# RF-detector.net
KiCad netlist of a schematic drawn in EAGLE
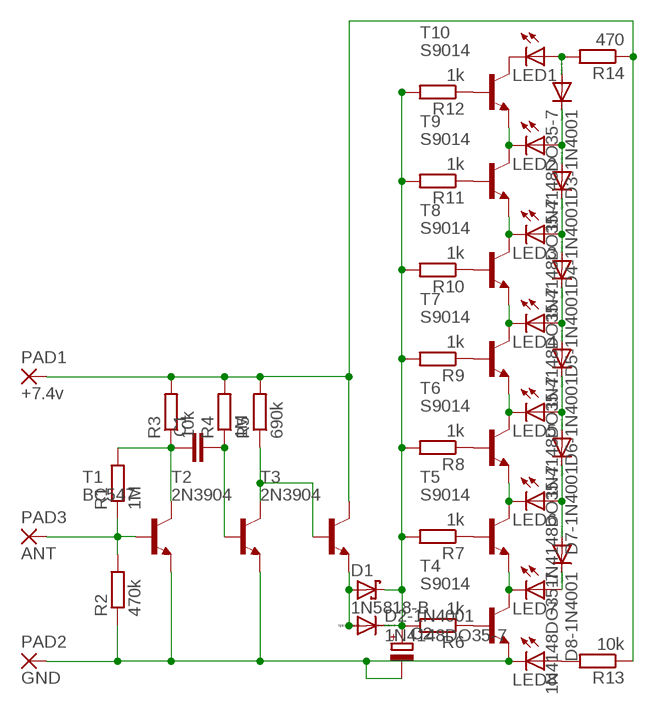
[diagram p0: schematic, sheet 1]

(export (version "E")
  (design (tool "Eeschema 10.0.6"))
  (components
    (comp (ref "C1")
      (value "C-EU050-024X044")
      (footprint "eagle-import:C050-024X044")
      (libsource (lib "eagle-import") (part "C-EU050-024X044"))
    )
    (comp (ref "C2")
      (value "CPOL-EUE1.8-4")
      (footprint "eagle-import:E1,8-4")
      (libsource (lib "eagle-import") (part "CPOL-EUE1.8-4"))
    )
    (comp (ref "D1")
      (value "1N5818-B")
      (footprint "eagle-import:DO41-7.6")
      (libsource (lib "eagle-import") (part "1N5818-B"))
    )
    (comp (ref "D2-1N4001")
      (value "1N4148DO35-7")
      (footprint "eagle-import:DO35-7")
      (libsource (lib "eagle-import") (part "1N4148DO35-7"))
    )
    (comp (ref "D3-1N4001")
      (value "1N4148DO35-7")
      (footprint "eagle-import:DO35-7")
      (libsource (lib "eagle-import") (part "1N4148DO35-7"))
    )
    (comp (ref "D4-1N4001")
      (value "1N4148DO35-7")
      (footprint "eagle-import:DO35-7")
      (libsource (lib "eagle-import") (part "1N4148DO35-7"))
    )
    (comp (ref "D5-1N4001")
      (value "1N4148DO35-7")
      (footprint "eagle-import:DO35-7")
      (libsource (lib "eagle-import") (part "1N4148DO35-7"))
    )
    (comp (ref "D6-1N4001")
      (value "1N4148DO35-7")
      (footprint "eagle-import:DO35-7")
      (libsource (lib "eagle-import") (part "1N4148DO35-7"))
    )
    (comp (ref "D7-1N4001")
      (value "1N4148DO35-7")
      (footprint "eagle-import:DO35-7")
      (libsource (lib "eagle-import") (part "1N4148DO35-7"))
    )
    (comp (ref "D8-1N4001")
      (value "1N4148DO35-7")
      (footprint "eagle-import:DO35-7")
      (libsource (lib "eagle-import") (part "1N4148DO35-7"))
    )
    (comp (ref "LED1")
      (value "LED3MM")
      (footprint "eagle-import:LED3MM")
      (libsource (lib "eagle-import") (part "LED3MM"))
    )
    (comp (ref "LED2")
      (value "LED3MM")
      (footprint "eagle-import:LED3MM")
      (libsource (lib "eagle-import") (part "LED3MM"))
    )
    (comp (ref "LED3")
      (value "LED3MM")
      (footprint "eagle-import:LED3MM")
      (libsource (lib "eagle-import") (part "LED3MM"))
    )
    (comp (ref "LED4")
      (value "LED3MM")
      (footprint "eagle-import:LED3MM")
      (libsource (lib "eagle-import") (part "LED3MM"))
    )
    (comp (ref "LED5")
      (value "LED3MM")
      (footprint "eagle-import:LED3MM")
      (libsource (lib "eagle-import") (part "LED3MM"))
    )
    (comp (ref "LED6")
      (value "LED3MM")
      (footprint "eagle-import:LED3MM")
      (libsource (lib "eagle-import") (part "LED3MM"))
    )
    (comp (ref "LED7")
      (value "LED3MM")
      (footprint "eagle-import:LED3MM")
      (libsource (lib "eagle-import") (part "LED3MM"))
    )
    (comp (ref "LED8")
      (value "LED3MM")
      (footprint "eagle-import:LED3MM")
      (libsource (lib "eagle-import") (part "LED3MM"))
    )
    (comp (ref "PAD1")
      (value "+7.4v")
      (footprint "eagle-import:2,54_0,8")
      (libsource (lib "eagle-import") (part "2,54/0,8"))
    )
    (comp (ref "PAD2")
      (value "GND")
      (footprint "eagle-import:2,54_0,8")
      (libsource (lib "eagle-import") (part "2,54/0,8"))
    )
    (comp (ref "PAD3")
      (value "ANT")
      (footprint "eagle-import:2,54_0,8")
      (libsource (lib "eagle-import") (part "2,54/0,8"))
    )
    (comp (ref "R1")
      (value "1M")
      (footprint "eagle-import:0204_7")
      (libsource (lib "eagle-import") (part "R-EU_0204/7"))
    )
    (comp (ref "R2")
      (value "470k")
      (footprint "eagle-import:0204_7")
      (libsource (lib "eagle-import") (part "R-EU_0204/7"))
    )
    (comp (ref "R3")
      (value "10k")
      (footprint "eagle-import:0204_7")
      (libsource (lib "eagle-import") (part "R-EU_0204/7"))
    )
    (comp (ref "R4")
      (value "1M")
      (footprint "eagle-import:0204_7")
      (libsource (lib "eagle-import") (part "R-EU_0204/7"))
    )
    (comp (ref "R5")
      (value "690k")
      (footprint "eagle-import:0204_7")
      (libsource (lib "eagle-import") (part "R-EU_0204/7"))
    )
    (comp (ref "R6")
      (value "1k")
      (footprint "eagle-import:0204_7")
      (libsource (lib "eagle-import") (part "R-EU_0204/7"))
    )
    (comp (ref "R7")
      (value "1k")
      (footprint "eagle-import:0204_7")
      (libsource (lib "eagle-import") (part "R-EU_0204/7"))
    )
    (comp (ref "R8")
      (value "1k")
      (footprint "eagle-import:0204_7")
      (libsource (lib "eagle-import") (part "R-EU_0204/7"))
    )
    (comp (ref "R9")
      (value "1k")
      (footprint "eagle-import:0204_7")
      (libsource (lib "eagle-import") (part "R-EU_0204/7"))
    )
    (comp (ref "R10")
      (value "1k")
      (footprint "eagle-import:0204_7")
      (libsource (lib "eagle-import") (part "R-EU_0204/7"))
    )
    (comp (ref "R11")
      (value "1k")
      (footprint "eagle-import:0204_7")
      (libsource (lib "eagle-import") (part "R-EU_0204/7"))
    )
    (comp (ref "R12")
      (value "1k")
      (footprint "eagle-import:0204_7")
      (libsource (lib "eagle-import") (part "R-EU_0204/7"))
    )
    (comp (ref "R13")
      (value "10k")
      (footprint "eagle-import:0204_7")
      (libsource (lib "eagle-import") (part "R-EU_0204/7"))
    )
    (comp (ref "R14")
      (value "470")
      (footprint "eagle-import:0204_7")
      (libsource (lib "eagle-import") (part "R-EU_0204/7"))
    )
    (comp (ref "T1")
      (value "BC547")
      (footprint "eagle-import:TO92")
      (libsource (lib "eagle-import") (part "BC547"))
    )
    (comp (ref "T2")
      (value "2N3904")
      (footprint "eagle-import:TO92")
      (libsource (lib "eagle-import") (part "2N3904"))
    )
    (comp (ref "T3")
      (value "2N3904")
      (footprint "eagle-import:TO92")
      (libsource (lib "eagle-import") (part "2N3904"))
    )
    (comp (ref "T4")
      (value "S9014")
      (footprint "eagle-import:TO92-EBC")
      (libsource (lib "eagle-import") (part "-NPN-TO92-EBC"))
    )
    (comp (ref "T5")
      (value "S9014")
      (footprint "eagle-import:TO92-EBC")
      (libsource (lib "eagle-import") (part "-NPN-TO92-EBC"))
    )
    (comp (ref "T6")
      (value "S9014")
      (footprint "eagle-import:TO92-EBC")
      (libsource (lib "eagle-import") (part "-NPN-TO92-EBC"))
    )
    (comp (ref "T7")
      (value "S9014")
      (footprint "eagle-import:TO92-EBC")
      (libsource (lib "eagle-import") (part "-NPN-TO92-EBC"))
    )
    (comp (ref "T8")
      (value "S9014")
      (footprint "eagle-import:TO92-EBC")
      (libsource (lib "eagle-import") (part "-NPN-TO92-EBC"))
    )
    (comp (ref "T9")
      (value "S9014")
      (footprint "eagle-import:TO92-EBC")
      (libsource (lib "eagle-import") (part "-NPN-TO92-EBC"))
    )
    (comp (ref "T10")
      (value "S9014")
      (footprint "eagle-import:TO92-EBC")
      (libsource (lib "eagle-import") (part "-NPN-TO92-EBC"))
    )
  )
  (nets
    (net (code "1") (name "Net-(C2-Pad+)") (class "Default")
      (node (ref "C2") (pin "+") (pinfunction "+_+") (pintype "passive"))
      (node (ref "D1") (pin "C") (pinfunction "C_C") (pintype "passive"))
      (node (ref "D2-1N4001") (pin "C") (pinfunction "C_C") (pintype "passive"))
      (node (ref "R10") (pin "2") (pinfunction "2_2") (pintype "passive"))
      (node (ref "R11") (pin "2") (pinfunction "2_2") (pintype "passive"))
      (node (ref "R12") (pin "2") (pinfunction "2_2") (pintype "passive"))
      (node (ref "R6") (pin "2") (pinfunction "2_2") (pintype "passive"))
      (node (ref "R7") (pin "2") (pinfunction "2_2") (pintype "passive"))
      (node (ref "R8") (pin "2") (pinfunction "2_2") (pintype "passive"))
      (node (ref "R9") (pin "2") (pinfunction "2_2") (pintype "passive"))
    )
    (net (code "2") (name "Net-(D3-1N4001-PadA)") (class "Default")
      (node (ref "D3-1N4001") (pin "A") (pinfunction "A_A") (pintype "passive"))
      (node (ref "LED1") (pin "A") (pinfunction "A_A") (pintype "passive"))
      (node (ref "R14") (pin "2") (pinfunction "2_2") (pintype "passive"))
    )
    (net (code "3") (name "Net-(D3-1N4001-PadC)") (class "Default")
      (node (ref "D3-1N4001") (pin "C") (pinfunction "C_C") (pintype "passive"))
      (node (ref "D4-1N4001") (pin "A") (pinfunction "A_A") (pintype "passive"))
      (node (ref "LED2") (pin "A") (pinfunction "A_A") (pintype "passive"))
    )
    (net (code "4") (name "Net-(D4-1N4001-PadC)") (class "Default")
      (node (ref "D4-1N4001") (pin "C") (pinfunction "C_C") (pintype "passive"))
      (node (ref "D5-1N4001") (pin "A") (pinfunction "A_A") (pintype "passive"))
      (node (ref "LED3") (pin "A") (pinfunction "A_A") (pintype "passive"))
    )
    (net (code "5") (name "Net-(D5-1N4001-PadC)") (class "Default")
      (node (ref "D5-1N4001") (pin "C") (pinfunction "C_C") (pintype "passive"))
      (node (ref "D6-1N4001") (pin "A") (pinfunction "A_A") (pintype "passive"))
      (node (ref "LED4") (pin "A") (pinfunction "A_A") (pintype "passive"))
    )
    (net (code "6") (name "Net-(D6-1N4001-PadC)") (class "Default")
      (node (ref "D6-1N4001") (pin "C") (pinfunction "C_C") (pintype "passive"))
      (node (ref "D7-1N4001") (pin "A") (pinfunction "A_A") (pintype "passive"))
      (node (ref "LED5") (pin "A") (pinfunction "A_A") (pintype "passive"))
    )
    (net (code "7") (name "Net-(D7-1N4001-PadC)") (class "Default")
      (node (ref "D7-1N4001") (pin "C") (pinfunction "C_C") (pintype "passive"))
      (node (ref "D8-1N4001") (pin "A") (pinfunction "A_A") (pintype "passive"))
      (node (ref "LED6") (pin "A") (pinfunction "A_A") (pintype "passive"))
    )
    (net (code "8") (name "Net-(D8-1N4001-PadC)") (class "Default")
      (node (ref "D8-1N4001") (pin "C") (pinfunction "C_C") (pintype "passive"))
      (node (ref "LED7") (pin "A") (pinfunction "A_A") (pintype "passive"))
    )
    (net (code "9") (name "Net-(LED1-C)") (class "Default")
      (node (ref "LED1") (pin "K") (pinfunction "C_K") (pintype "passive"))
      (node (ref "T10") (pin "C") (pinfunction "C_C") (pintype "passive"))
    )
    (net (code "10") (name "Net-(LED2-C)") (class "Default")
      (node (ref "LED2") (pin "K") (pinfunction "C_K") (pintype "passive"))
      (node (ref "T10") (pin "E") (pinfunction "E_E") (pintype "passive"))
      (node (ref "T9") (pin "C") (pinfunction "C_C") (pintype "passive"))
    )
    (net (code "11") (name "Net-(LED3-C)") (class "Default")
      (node (ref "LED3") (pin "K") (pinfunction "C_K") (pintype "passive"))
      (node (ref "T8") (pin "C") (pinfunction "C_C") (pintype "passive"))
      (node (ref "T9") (pin "E") (pinfunction "E_E") (pintype "passive"))
    )
    (net (code "12") (name "Net-(LED4-C)") (class "Default")
      (node (ref "LED4") (pin "K") (pinfunction "C_K") (pintype "passive"))
      (node (ref "T7") (pin "C") (pinfunction "C_C") (pintype "passive"))
      (node (ref "T8") (pin "E") (pinfunction "E_E") (pintype "passive"))
    )
    (net (code "13") (name "Net-(LED5-C)") (class "Default")
      (node (ref "LED5") (pin "K") (pinfunction "C_K") (pintype "passive"))
      (node (ref "T6") (pin "C") (pinfunction "C_C") (pintype "passive"))
      (node (ref "T7") (pin "E") (pinfunction "E_E") (pintype "passive"))
    )
    (net (code "14") (name "Net-(LED6-C)") (class "Default")
      (node (ref "LED6") (pin "K") (pinfunction "C_K") (pintype "passive"))
      (node (ref "T5") (pin "C") (pinfunction "C_C") (pintype "passive"))
      (node (ref "T6") (pin "E") (pinfunction "E_E") (pintype "passive"))
    )
    (net (code "15") (name "Net-(LED7-C)") (class "Default")
      (node (ref "LED7") (pin "K") (pinfunction "C_K") (pintype "passive"))
      (node (ref "T4") (pin "C") (pinfunction "C_C") (pintype "passive"))
      (node (ref "T5") (pin "E") (pinfunction "E_E") (pintype "passive"))
    )
    (net (code "16") (name "Net-(LED8-C)") (class "Default")
      (node (ref "C2") (pin "-") (pinfunction "-_-") (pintype "passive"))
      (node (ref "LED8") (pin "K") (pinfunction "C_K") (pintype "passive"))
      (node (ref "PAD2") (pin "1") (pinfunction "P_1") (pintype "passive"))
      (node (ref "R2") (pin "1") (pinfunction "1_1") (pintype "passive"))
      (node (ref "T1") (pin "1") (pinfunction "E_1") (pintype "passive"))
      (node (ref "T2") (pin "3") (pinfunction "E_3") (pintype "passive"))
      (node (ref "T4") (pin "E") (pinfunction "E_E") (pintype "passive"))
    )
    (net (code "17") (name "Net-(LED8-PadA)") (class "Default")
      (node (ref "LED8") (pin "A") (pinfunction "A_A") (pintype "passive"))
      (node (ref "R13") (pin "2") (pinfunction "2_2") (pintype "passive"))
    )
    (net (code "18") (name "Net-(PAD1-P)") (class "Default")
      (node (ref "PAD1") (pin "1") (pinfunction "P_1") (pintype "passive"))
      (node (ref "R13") (pin "1") (pinfunction "1_1") (pintype "passive"))
      (node (ref "R14") (pin "1") (pinfunction "1_1") (pintype "passive"))
      (node (ref "R3") (pin "2") (pinfunction "2_2") (pintype "passive"))
      (node (ref "R4") (pin "2") (pinfunction "2_2") (pintype "passive"))
      (node (ref "R5") (pin "2") (pinfunction "2_2") (pintype "passive"))
      (node (ref "T3") (pin "1") (pinfunction "C_1") (pintype "passive"))
    )
    (net (code "19") (name "Net-(PAD3-P)") (class "Default")
      (node (ref "PAD3") (pin "1") (pinfunction "P_1") (pintype "passive"))
      (node (ref "R1") (pin "1") (pinfunction "1_1") (pintype "passive"))
      (node (ref "R2") (pin "2") (pinfunction "2_2") (pintype "passive"))
      (node (ref "T1") (pin "2") (pinfunction "B_2") (pintype "passive"))
    )
    (net (code "20") (name "Net-(R6-Pad1)") (class "Default")
      (node (ref "R6") (pin "1") (pinfunction "1_1") (pintype "passive"))
      (node (ref "T4") (pin "B") (pinfunction "B_B") (pintype "passive"))
    )
    (net (code "21") (name "Net-(R7-Pad1)") (class "Default")
      (node (ref "R7") (pin "1") (pinfunction "1_1") (pintype "passive"))
      (node (ref "T5") (pin "B") (pinfunction "B_B") (pintype "passive"))
    )
    (net (code "22") (name "Net-(R8-Pad1)") (class "Default")
      (node (ref "R8") (pin "1") (pinfunction "1_1") (pintype "passive"))
      (node (ref "T6") (pin "B") (pinfunction "B_B") (pintype "passive"))
    )
    (net (code "23") (name "Net-(R9-Pad1)") (class "Default")
      (node (ref "R9") (pin "1") (pinfunction "1_1") (pintype "passive"))
      (node (ref "T7") (pin "B") (pinfunction "B_B") (pintype "passive"))
    )
    (net (code "24") (name "Net-(R10-Pad1)") (class "Default")
      (node (ref "R10") (pin "1") (pinfunction "1_1") (pintype "passive"))
      (node (ref "T8") (pin "B") (pinfunction "B_B") (pintype "passive"))
    )
    (net (code "25") (name "Net-(R11-Pad1)") (class "Default")
      (node (ref "R11") (pin "1") (pinfunction "1_1") (pintype "passive"))
      (node (ref "T9") (pin "B") (pinfunction "B_B") (pintype "passive"))
    )
    (net (code "26") (name "Net-(R12-Pad1)") (class "Default")
      (node (ref "R12") (pin "1") (pinfunction "1_1") (pintype "passive"))
      (node (ref "T10") (pin "B") (pinfunction "B_B") (pintype "passive"))
    )
    (net (code "27") (name "Net-(T1-C)") (class "Default")
      (node (ref "C1") (pin "1") (pinfunction "1_1") (pintype "passive"))
      (node (ref "R1") (pin "2") (pinfunction "2_2") (pintype "passive"))
      (node (ref "R3") (pin "1") (pinfunction "1_1") (pintype "passive"))
      (node (ref "T1") (pin "3") (pinfunction "C_3") (pintype "passive"))
    )
    (net (code "28") (name "Net-(T2-B)") (class "Default")
      (node (ref "C1") (pin "2") (pinfunction "2_2") (pintype "passive"))
      (node (ref "R4") (pin "1") (pinfunction "1_1") (pintype "passive"))
      (node (ref "T2") (pin "2") (pinfunction "B_2") (pintype "passive"))
    )
    (net (code "29") (name "Net-(T2-C)") (class "Default")
      (node (ref "R5") (pin "1") (pinfunction "1_1") (pintype "passive"))
      (node (ref "T2") (pin "1") (pinfunction "C_1") (pintype "passive"))
      (node (ref "T3") (pin "2") (pinfunction "B_2") (pintype "passive"))
    )
    (net (code "30") (name "Net-(T3-E)") (class "Default")
      (node (ref "D1") (pin "A") (pinfunction "A_A") (pintype "passive"))
      (node (ref "D2-1N4001") (pin "A") (pinfunction "A_A") (pintype "passive"))
      (node (ref "T3") (pin "3") (pinfunction "E_3") (pintype "passive"))
    )
  )
)
